# led_breakout.net
KiCad netlist of a schematic drawn in EAGLE
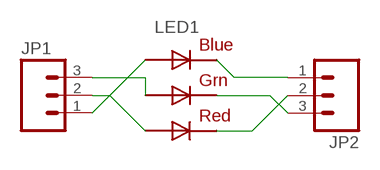
[diagram p0: schematic, sheet 1]

(export (version "E")
  (design (tool "Eeschema 10.0.6"))
  (components
    (comp (ref "JP1")
      (value "M03PTH")
      (footprint "eagle-import:1X03")
      (libsource (lib "eagle-import") (part "M03PTH"))
    )
    (comp (ref "JP2")
      (value "M03PTH")
      (footprint "eagle-import:1X03")
      (libsource (lib "eagle-import") (part "M03PTH"))
    )
    (comp (ref "LED1")
      (value "RGBLED5050")
      (footprint "eagle-import:RGBLED5050")
      (libsource (lib "eagle-import") (part "RGBLED5050"))
    )
  )
  (nets
    (net (code "1") (name "Net-(LED1-BLUE_A)") (class "Default")
      (node (ref "JP1") (pin "1") (pinfunction "1_1") (pintype "passive"))
      (node (ref "LED1") (pin "3") (pinfunction "BLUE_A_3") (pintype "bidirectional"))
    )
    (net (code "2") (name "Net-(LED1-BLUE_C)") (class "Default")
      (node (ref "JP2") (pin "1") (pinfunction "1_1") (pintype "passive"))
      (node (ref "LED1") (pin "4") (pinfunction "BLUE_C_4") (pintype "bidirectional"))
    )
    (net (code "3") (name "Net-(LED1-GREEN_A)") (class "Default")
      (node (ref "JP1") (pin "3") (pinfunction "3_3") (pintype "passive"))
      (node (ref "LED1") (pin "1") (pinfunction "GREEN_A_1") (pintype "bidirectional"))
    )
    (net (code "4") (name "Net-(LED1-GREEN_C)") (class "Default")
      (node (ref "JP2") (pin "3") (pinfunction "3_3") (pintype "passive"))
      (node (ref "LED1") (pin "6") (pinfunction "GREEN_C_6") (pintype "bidirectional"))
    )
    (net (code "5") (name "Net-(LED1-RED_A)") (class "Default")
      (node (ref "JP1") (pin "2") (pinfunction "2_2") (pintype "passive"))
      (node (ref "LED1") (pin "2") (pinfunction "RED_A_2") (pintype "bidirectional"))
    )
    (net (code "6") (name "Net-(LED1-RED_C)") (class "Default")
      (node (ref "JP2") (pin "2") (pinfunction "2_2") (pintype "passive"))
      (node (ref "LED1") (pin "5") (pinfunction "RED_C_5") (pintype "bidirectional"))
    )
  )
)
